# DUAL_IO_TTL_BUFFER.net
KiCad netlist of a schematic drawn in Altium Designer
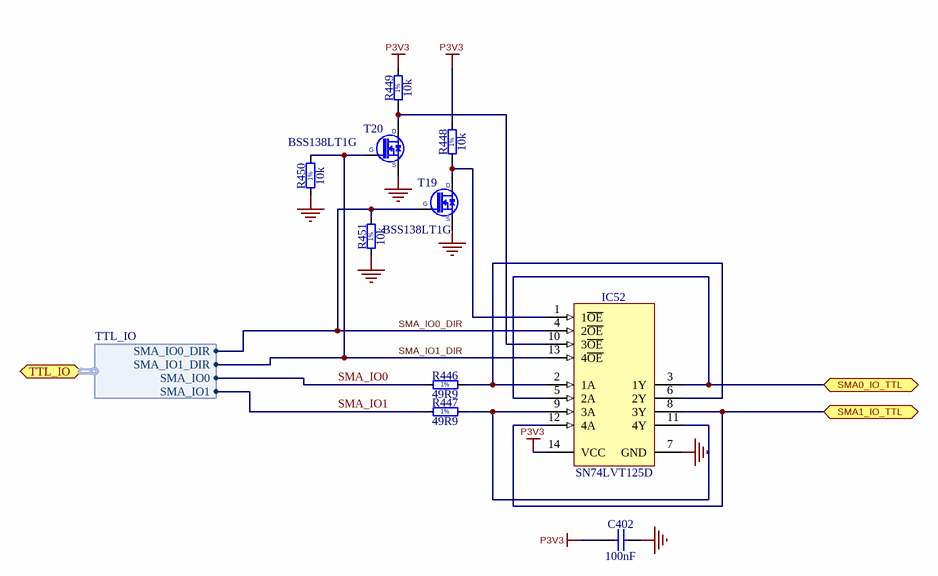
[diagram p0: DUAL_IO_TTL_BUFFER.SchDoc]

(export (version "E")
  (design (tool "Eeschema 10.0.6"))
  (components
    (comp (ref "C402")
      (value "100nF")
      (footprint "CAPC0603X33N")
      (description "Non-polarised capacitor")
      (fields
        (field (name "MANUFACTURER PART NUMBER") "CC0201_100NF_6.3V_10%_X5R")
        (field (name "MANUFACTURER") "GENERIC")
        (field (name "AUTHOR") "CERN DEM JLC")
      )
      (libsource (lib "Capacitors") (part "Capacitor - non polarized"))
    )
    (comp (ref "IC52")
      (value "SN74LVT125D")
      (footprint "SOIC127P600X175-14N")
      (description "Quadruple Bus Buffer with 3-State Outputs")
      (fields (field (name "MANUFACTURER") "TEXAS INSTRUMENTS") (field (name "AUTHOR") "CERN DEM JLC"))
      (libsource (lib "ICs And Semiconductors") (part "74125"))
    )
    (comp (ref "R446")
      (value "49R9")
      (footprint "RESC1005X40N")
      (description "Resistor - 1%")
      (fields
        (field (name "MANUFACTURER PART NUMBER") "R0402_49R9_1%_0.0625W_100PPM")
        (field (name "MANUFACTURER") "GENERIC")
        (field (name "AUTHOR") "CERN DEM JLC")
      )
      (libsource (lib "Resistors") (part "Resistor - 1%"))
    )
    (comp (ref "R447")
      (value "49R9")
      (footprint "RESC1005X40N")
      (description "Resistor - 1%")
      (fields
        (field (name "MANUFACTURER PART NUMBER") "R0402_49R9_1%_0.0625W_100PPM")
        (field (name "MANUFACTURER") "GENERIC")
        (field (name "AUTHOR") "CERN DEM JLC")
      )
      (libsource (lib "Resistors") (part "Resistor - 1%"))
    )
    (comp (ref "R448")
      (value "10k")
      (footprint "RESC1005X40N")
      (description "Resistor - 1%")
      (fields
        (field (name "MANUFACTURER PART NUMBER") "R0402_10K_1%_0.0625W_100PPM")
        (field (name "MANUFACTURER") "GENERIC")
        (field (name "AUTHOR") "CERN DEM JLC")
      )
      (libsource (lib "Resistors") (part "Resistor - 1%"))
    )
    (comp (ref "R449")
      (value "10k")
      (footprint "RESC1005X40N")
      (description "Resistor - 1%")
      (fields
        (field (name "MANUFACTURER PART NUMBER") "R0402_10K_1%_0.0625W_100PPM")
        (field (name "MANUFACTURER") "GENERIC")
        (field (name "AUTHOR") "CERN DEM JLC")
      )
      (libsource (lib "Resistors") (part "Resistor - 1%"))
    )
    (comp (ref "R450")
      (value "10k")
      (footprint "RESC1005X40N")
      (description "Resistor - 1%")
      (fields
        (field (name "MANUFACTURER PART NUMBER") "R0402_10K_1%_0.0625W_100PPM")
        (field (name "MANUFACTURER") "GENERIC")
        (field (name "AUTHOR") "CERN DEM JLC")
      )
      (libsource (lib "Resistors") (part "Resistor - 1%"))
    )
    (comp (ref "R451")
      (value "10k")
      (footprint "RESC1005X40N")
      (description "Resistor - 1%")
      (fields
        (field (name "MANUFACTURER PART NUMBER") "R0402_10K_1%_0.0625W_100PPM")
        (field (name "MANUFACTURER") "GENERIC")
        (field (name "AUTHOR") "CERN DEM JLC")
      )
      (libsource (lib "Resistors") (part "Resistor - 1%"))
    )
    (comp (ref "T19")
      (value "BSS138LT1G")
      (footprint "SOT95P240X110-3N")
      (description "N-CHANNEL MOSFET WITH DIODE")
      (fields (field (name "MANUFACTURER") "ON SEMICONDUCTOR") (field (name "AUTHOR") "CERN DEM JLC"))
      (libsource (lib "ICs And Semiconductors") (part "N-MOSFET-D 1G 2S 3D"))
    )
    (comp (ref "T20")
      (value "BSS138LT1G")
      (footprint "SOT95P240X110-3N")
      (description "N-CHANNEL MOSFET WITH DIODE")
      (fields (field (name "MANUFACTURER") "ON SEMICONDUCTOR") (field (name "AUTHOR") "CERN DEM JLC"))
      (libsource (lib "ICs And Semiconductors") (part "N-MOSFET-D 1G 2S 3D"))
    )
  )
  (nets
    (net (code "2") (name "/SMA0_IO_TTL") (class "Default")
      (node (ref "IC52") (pin "3") (pinfunction "1Y_3") (pintype "tri_state"))
      (node (ref "IC52") (pin "5") (pinfunction "2A_5") (pintype "input"))
    )
    (net (code "3") (name "/SMA1_IO_TTL") (class "Default")
      (node (ref "IC52") (pin "12") (pinfunction "4A_12") (pintype "input"))
      (node (ref "IC52") (pin "8") (pinfunction "3Y_8") (pintype "tri_state"))
    )
    (net (code "4") (name "/SMA_IO0") (class "Default")
      (node (ref "R446") (pin "1") (pinfunction "1_1") (pintype "passive"))
    )
    (net (code "5") (name "/SMA_IO0_DIR") (class "Default")
      (node (ref "IC52") (pin "4") (pinfunction "2~{OE}_4") (pintype "input"))
      (node (ref "R451") (pin "2") (pinfunction "2_2") (pintype "passive"))
      (node (ref "T19") (pin "1") (pinfunction "G_1") (pintype "passive"))
    )
    (net (code "6") (name "/SMA_IO1") (class "Default")
      (node (ref "R447") (pin "1") (pinfunction "1_1") (pintype "passive"))
    )
    (net (code "7") (name "/SMA_IO1_DIR") (class "Default")
      (node (ref "IC52") (pin "13") (pinfunction "4~{OE}_13") (pintype "input"))
      (node (ref "R450") (pin "2") (pinfunction "2_2") (pintype "passive"))
      (node (ref "T20") (pin "1") (pinfunction "G_1") (pintype "passive"))
    )
    (net (code "9") (name "GND") (class "Default")
      (node (ref "C402") (pin "2") (pinfunction "2_2") (pintype "passive"))
      (node (ref "IC52") (pin "7") (pinfunction "GND_7") (pintype "power_in"))
      (node (ref "R450") (pin "1") (pinfunction "1_1") (pintype "passive"))
      (node (ref "R451") (pin "1") (pinfunction "1_1") (pintype "passive"))
      (node (ref "T19") (pin "2") (pinfunction "S_2") (pintype "passive"))
      (node (ref "T20") (pin "2") (pinfunction "S_2") (pintype "passive"))
    )
    (net (code "10") (name "Net-(IC52-1A)") (class "Default")
      (node (ref "IC52") (pin "2") (pinfunction "1A_2") (pintype "input"))
      (node (ref "IC52") (pin "6") (pinfunction "2Y_6") (pintype "tri_state"))
      (node (ref "R446") (pin "2") (pinfunction "2_2") (pintype "passive"))
    )
    (net (code "11") (name "Net-(IC52-1~{OE})") (class "Default")
      (node (ref "IC52") (pin "1") (pinfunction "1~{OE}_1") (pintype "input"))
      (node (ref "R448") (pin "1") (pinfunction "1_1") (pintype "passive"))
      (node (ref "T19") (pin "3") (pinfunction "D_3") (pintype "passive"))
    )
    (net (code "12") (name "Net-(IC52-3A)") (class "Default")
      (node (ref "IC52") (pin "11") (pinfunction "4Y_11") (pintype "tri_state"))
      (node (ref "IC52") (pin "9") (pinfunction "3A_9") (pintype "input"))
      (node (ref "R447") (pin "2") (pinfunction "2_2") (pintype "passive"))
    )
    (net (code "13") (name "Net-(IC52-3~{OE})") (class "Default")
      (node (ref "IC52") (pin "10") (pinfunction "3~{OE}_10") (pintype "input"))
      (node (ref "R449") (pin "1") (pinfunction "1_1") (pintype "passive"))
      (node (ref "T20") (pin "3") (pinfunction "D_3") (pintype "passive"))
    )
    (net (code "14") (name "P3V3") (class "Default")
      (node (ref "C402") (pin "1") (pinfunction "1_1") (pintype "passive"))
      (node (ref "IC52") (pin "14") (pinfunction "VCC_14") (pintype "power_in"))
      (node (ref "R448") (pin "2") (pinfunction "2_2") (pintype "passive"))
      (node (ref "R449") (pin "2") (pinfunction "2_2") (pintype "passive"))
    )
  )
)
